# BatteryPowerV2.net
KiCad netlist of a schematic drawn in EAGLE
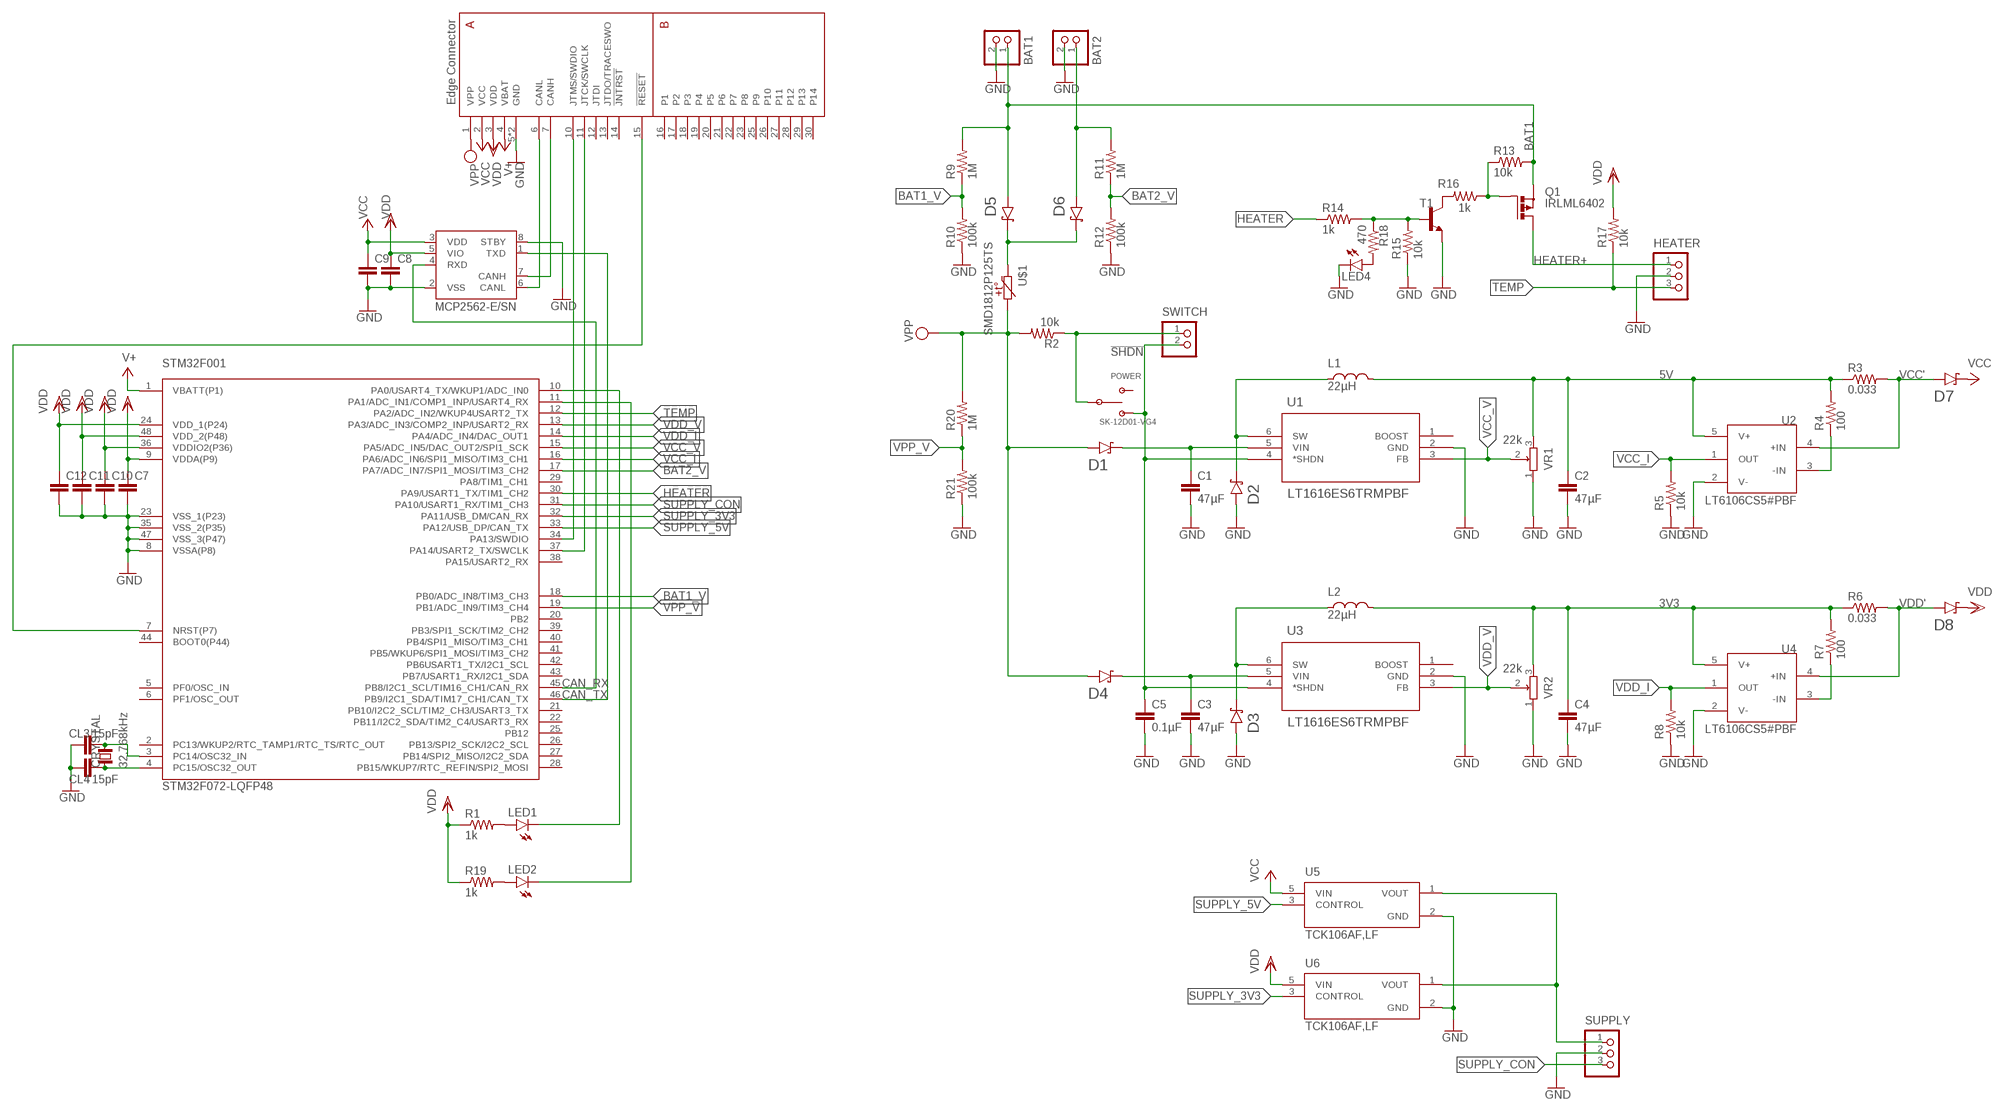
[diagram p0: schematic, sheet 1]

(export (version "E")
  (design (tool "Eeschema 10.0.6"))
  (components
    (comp (ref "BAT1")
      (value "S2B-XH-A")
      (footprint "eagle-import:S2B-XH-A")
      (libsource (lib "eagle-import") (part "S2B-XH-A"))
    )
    (comp (ref "BAT2")
      (value "S2B-XH-A")
      (footprint "eagle-import:S2B-XH-A")
      (libsource (lib "eagle-import") (part "S2B-XH-A"))
    )
    (comp (ref "C1")
      (value "47µF")
      (footprint "eagle-import:C0603")
      (libsource (lib "eagle-import") (part "C-EUC0603"))
    )
    (comp (ref "C2")
      (value "47µF")
      (footprint "eagle-import:C0603")
      (libsource (lib "eagle-import") (part "C-EUC0603"))
    )
    (comp (ref "C3")
      (value "47µF")
      (footprint "eagle-import:C0603")
      (libsource (lib "eagle-import") (part "C-EUC0603"))
    )
    (comp (ref "C4")
      (value "47µF")
      (footprint "eagle-import:C0603")
      (libsource (lib "eagle-import") (part "C-EUC0603"))
    )
    (comp (ref "C5")
      (value "0.1µF")
      (footprint "eagle-import:C0603")
      (libsource (lib "eagle-import") (part "C-EUC0603"))
    )
    (comp (ref "C7")
      (value "C-EUC0603K")
      (footprint "eagle-import:C0603K")
      (libsource (lib "eagle-import") (part "C-EUC0603K"))
    )
    (comp (ref "C8")
      (value "C-EUC0603K")
      (footprint "eagle-import:C0603K")
      (libsource (lib "eagle-import") (part "C-EUC0603K"))
    )
    (comp (ref "C9")
      (value "C-EUC0603K")
      (footprint "eagle-import:C0603K")
      (libsource (lib "eagle-import") (part "C-EUC0603K"))
    )
    (comp (ref "C10")
      (value "C-EUC0603K")
      (footprint "eagle-import:C0603K")
      (libsource (lib "eagle-import") (part "C-EUC0603K"))
    )
    (comp (ref "C11")
      (value "C-EUC0603K")
      (footprint "eagle-import:C0603K")
      (libsource (lib "eagle-import") (part "C-EUC0603K"))
    )
    (comp (ref "C12")
      (value "C-EUC0603K")
      (footprint "eagle-import:C0603K")
      (libsource (lib "eagle-import") (part "C-EUC0603K"))
    )
    (comp (ref "CL3")
      (value "15pF")
      (footprint "eagle-import:C0603K")
      (libsource (lib "eagle-import") (part "C-EUC0603K"))
    )
    (comp (ref "CL4")
      (value "15pF")
      (footprint "eagle-import:C0603K")
      (libsource (lib "eagle-import") (part "C-EUC0603K"))
    )
    (comp (ref "CRYSTAL")
      (value "32.768kHz")
      (footprint "eagle-import:FC-255")
      (libsource (lib "eagle-import") (part "CRYTALFC-255"))
    )
    (comp (ref "D1")
      (value "CUHS20S30")
      (footprint "eagle-import:CUHS20S30")
      (libsource (lib "eagle-import") (part "CUHS20S30"))
    )
    (comp (ref "D2")
      (value "CUHS20S30")
      (footprint "eagle-import:CUHS20S30")
      (libsource (lib "eagle-import") (part "CUHS20S30"))
    )
    (comp (ref "D3")
      (value "CUHS20S30")
      (footprint "eagle-import:CUHS20S30")
      (libsource (lib "eagle-import") (part "CUHS20S30"))
    )
    (comp (ref "D4")
      (value "CUHS20S30")
      (footprint "eagle-import:CUHS20S30")
      (libsource (lib "eagle-import") (part "CUHS20S30"))
    )
    (comp (ref "D5")
      (value "CUHS20S30")
      (footprint "eagle-import:CUHS20S30")
      (libsource (lib "eagle-import") (part "CUHS20S30"))
    )
    (comp (ref "D6")
      (value "CUHS20S30")
      (footprint "eagle-import:CUHS20S30")
      (libsource (lib "eagle-import") (part "CUHS20S30"))
    )
    (comp (ref "D7")
      (value "CUHS20S30")
      (footprint "eagle-import:CUHS20S30")
      (libsource (lib "eagle-import") (part "CUHS20S30"))
    )
    (comp (ref "D8")
      (value "CUHS20S30")
      (footprint "eagle-import:CUHS20S30")
      (libsource (lib "eagle-import") (part "CUHS20S30"))
    )
    (comp (ref "HEATER")
      (value "S3B-PH-K-S")
      (footprint "eagle-import:S3B-PH-K-S")
      (libsource (lib "eagle-import") (part "S3B-PH-K-S"))
    )
    (comp (ref "L1")
      (value "22µH")
      (footprint "eagle-import:NR10050")
      (libsource (lib "eagle-import") (part "NR10050"))
    )
    (comp (ref "L2")
      (value "22µH")
      (footprint "eagle-import:NR10050")
      (libsource (lib "eagle-import") (part "NR10050"))
    )
    (comp (ref "LED1")
      (value "LEDCHIP-LED0603")
      (footprint "eagle-import:CHIP-LED0603")
      (libsource (lib "eagle-import") (part "LEDCHIP-LED0603"))
    )
    (comp (ref "LED2")
      (value "LEDCHIP-LED0603")
      (footprint "eagle-import:CHIP-LED0603")
      (libsource (lib "eagle-import") (part "LEDCHIP-LED0603"))
    )
    (comp (ref "LED4")
      (value "LEDCHIPLED_0603")
      (footprint "eagle-import:CHIPLED_0603")
      (libsource (lib "eagle-import") (part "LEDCHIPLED_0603"))
    )
    (comp (ref "MCP2562")
      (value "MCP2562-E/SN")
      (footprint "eagle-import:SOIC127P600X175-8N")
      (fields (field (name "MF") "Microchip"))
      (libsource (lib "eagle-import") (part "MCP2562-E/SN"))
    )
    (comp (ref "POWER")
      (value "SK-12D01-VG4")
      (footprint "eagle-import:SK-12D01-VG4")
      (libsource (lib "eagle-import") (part "SK-12D01-VG4"))
    )
    (comp (ref "Q1")
      (value "IRLML6402")
      (footprint "eagle-import:SOT-23")
      (libsource (lib "eagle-import") (part "IRLML6402"))
    )
    (comp (ref "R1")
      (value "1k")
      (footprint "eagle-import:R0603")
      (libsource (lib "eagle-import") (part "R-US_R0603"))
    )
    (comp (ref "R2")
      (value "10k")
      (footprint "eagle-import:R0603")
      (libsource (lib "eagle-import") (part "R-US_R0603"))
    )
    (comp (ref "R3")
      (value "0.033")
      (footprint "eagle-import:R0603")
      (libsource (lib "eagle-import") (part "R-US_R0603"))
    )
    (comp (ref "R4")
      (value "100")
      (footprint "eagle-import:R0603")
      (libsource (lib "eagle-import") (part "R-US_R0603"))
    )
    (comp (ref "R5")
      (value "10k")
      (footprint "eagle-import:R0603")
      (libsource (lib "eagle-import") (part "R-US_R0603"))
    )
    (comp (ref "R6")
      (value "0.033")
      (footprint "eagle-import:R0603")
      (libsource (lib "eagle-import") (part "R-US_R0603"))
    )
    (comp (ref "R7")
      (value "100")
      (footprint "eagle-import:R0603")
      (libsource (lib "eagle-import") (part "R-US_R0603"))
    )
    (comp (ref "R8")
      (value "10k")
      (footprint "eagle-import:R0603")
      (libsource (lib "eagle-import") (part "R-US_R0603"))
    )
    (comp (ref "R9")
      (value "1M")
      (footprint "eagle-import:R0603")
      (libsource (lib "eagle-import") (part "R-US_R0603"))
    )
    (comp (ref "R10")
      (value "100k")
      (footprint "eagle-import:R0603")
      (libsource (lib "eagle-import") (part "R-US_R0603"))
    )
    (comp (ref "R11")
      (value "1M")
      (footprint "eagle-import:R0603")
      (libsource (lib "eagle-import") (part "R-US_R0603"))
    )
    (comp (ref "R12")
      (value "100k")
      (footprint "eagle-import:R0603")
      (libsource (lib "eagle-import") (part "R-US_R0603"))
    )
    (comp (ref "R13")
      (value "10k")
      (footprint "eagle-import:R0603")
      (libsource (lib "eagle-import") (part "R-US_R0603"))
    )
    (comp (ref "R14")
      (value "1k")
      (footprint "eagle-import:R0603")
      (libsource (lib "eagle-import") (part "R-US_R0603"))
    )
    (comp (ref "R15")
      (value "10k")
      (footprint "eagle-import:R0603")
      (libsource (lib "eagle-import") (part "R-US_R0603"))
    )
    (comp (ref "R16")
      (value "1k")
      (footprint "eagle-import:R0603")
      (libsource (lib "eagle-import") (part "R-US_R0603"))
    )
    (comp (ref "R17")
      (value "10k")
      (footprint "eagle-import:R0603")
      (libsource (lib "eagle-import") (part "R-US_R0603"))
    )
    (comp (ref "R18")
      (value "470")
      (footprint "eagle-import:R0603")
      (libsource (lib "eagle-import") (part "R-US_R0603"))
    )
    (comp (ref "R19")
      (value "1k")
      (footprint "eagle-import:R0603")
      (libsource (lib "eagle-import") (part "R-US_R0603"))
    )
    (comp (ref "R20")
      (value "1M")
      (footprint "eagle-import:R0603")
      (libsource (lib "eagle-import") (part "R-US_R0603"))
    )
    (comp (ref "R21")
      (value "100k")
      (footprint "eagle-import:R0603")
      (libsource (lib "eagle-import") (part "R-US_R0603"))
    )
    (comp (ref "STM32F001")
      (value "STM32F072-LQFP48")
      (footprint "eagle-import:LQFP48")
      (libsource (lib "eagle-import") (part "STM32F072-LQFP48"))
    )
    (comp (ref "SUPPLY")
      (value "S3B-PH-K-S")
      (footprint "eagle-import:S3B-PH-K-S")
      (libsource (lib "eagle-import") (part "S3B-PH-K-S"))
    )
    (comp (ref "SWITCH")
      (value "S2B-PH-K-S")
      (footprint "eagle-import:S2B-PH-K-S")
      (libsource (lib "eagle-import") (part "S2B-PH-K-S"))
    )
    (comp (ref "T1")
      (value "-NPN-SOT23-EBC")
      (footprint "eagle-import:SOT23-EBC")
      (libsource (lib "eagle-import") (part "-NPN-SOT23-EBC"))
    )
    (comp (ref "U$1")
      (value "SMD1812P125TS")
      (footprint "eagle-import:SMD1812P")
      (libsource (lib "eagle-import") (part "SMD1812P125TS"))
    )
    (comp (ref "U$2")
      (value "EDGE30")
      (footprint "eagle-import:EDGE30")
      (libsource (lib "eagle-import") (part "EDGE30"))
    )
    (comp (ref "U1")
      (value "LT1616ES6TRMPBF")
      (footprint "eagle-import:SOT-6_S")
      (fields (field (name "MF") "Analog Devices") (field (name "MP") "LT1616ES6#TRMPBF"))
      (libsource (lib "eagle-import") (part "LT1616ES6TRMPBF"))
    )
    (comp (ref "U2")
      (value "LT6106CS5#PBF")
      (footprint "eagle-import:SOT95P280X100-5N_LT6106CS5#PBF")
      (fields (field (name "MF") "Linear Technology"))
      (libsource (lib "eagle-import") (part "LT6106CS5#PBF"))
    )
    (comp (ref "U3")
      (value "LT1616ES6TRMPBF")
      (footprint "eagle-import:SOT-6_S")
      (fields (field (name "MF") "Analog Devices") (field (name "MP") "LT1616ES6#TRMPBF"))
      (libsource (lib "eagle-import") (part "LT1616ES6TRMPBF"))
    )
    (comp (ref "U4")
      (value "LT6106CS5#PBF")
      (footprint "eagle-import:SOT95P280X100-5N_LT6106CS5#PBF")
      (fields (field (name "MF") "Linear Technology"))
      (libsource (lib "eagle-import") (part "LT6106CS5#PBF"))
    )
    (comp (ref "U5")
      (value "TCK106AF,LF")
      (footprint "eagle-import:IC_TCK106AF,LF")
      (fields (field (name "MF") "Toshiba Semiconductor"))
      (libsource (lib "eagle-import") (part "TCK106AF,LF"))
    )
    (comp (ref "U6")
      (value "TCK106AF,LF")
      (footprint "eagle-import:IC_TCK106AF,LF")
      (fields (field (name "MF") "Toshiba Semiconductor"))
      (libsource (lib "eagle-import") (part "TCK106AF,LF"))
    )
    (comp (ref "VR1")
      (value "22k")
      (footprint "eagle-import:PVZ3A")
      (libsource (lib "eagle-import") (part "PVZ3A"))
    )
    (comp (ref "VR2")
      (value "22k")
      (footprint "eagle-import:PVZ3A")
      (libsource (lib "eagle-import") (part "PVZ3A"))
    )
  )
  (nets
    (net (code "1") (name "/3V3") (class "Default")
      (node (ref "C4") (pin "1") (pinfunction "1_1") (pintype "passive"))
      (node (ref "L2") (pin "2") (pinfunction "2_2") (pintype "bidirectional"))
      (node (ref "R6") (pin "1") (pinfunction "1_1") (pintype "passive"))
      (node (ref "R7") (pin "2") (pinfunction "2_2") (pintype "passive"))
      (node (ref "U4") (pin "5") (pinfunction "V+_5") (pintype "power_in"))
      (node (ref "VR2") (pin "3") (pinfunction "3_3") (pintype "bidirectional"))
    )
    (net (code "2") (name "/5V") (class "Default")
      (node (ref "C2") (pin "1") (pinfunction "1_1") (pintype "passive"))
      (node (ref "L1") (pin "2") (pinfunction "2_2") (pintype "bidirectional"))
      (node (ref "R3") (pin "1") (pinfunction "1_1") (pintype "passive"))
      (node (ref "R4") (pin "2") (pinfunction "2_2") (pintype "passive"))
      (node (ref "U2") (pin "5") (pinfunction "V+_5") (pintype "power_in"))
      (node (ref "VR1") (pin "3") (pinfunction "3_3") (pintype "bidirectional"))
    )
    (net (code "3") (name "/BAT1") (class "Default")
      (node (ref "BAT1") (pin "1") (pinfunction "1_1") (pintype "passive"))
      (node (ref "D5") (pin "A") (pinfunction "A_A") (pintype "bidirectional"))
      (node (ref "Q1") (pin "P2") (pinfunction "S_P2") (pintype "passive"))
      (node (ref "R13") (pin "2") (pinfunction "2_2") (pintype "passive"))
      (node (ref "R9") (pin "2") (pinfunction "2_2") (pintype "passive"))
    )
    (net (code "4") (name "/CAN_RX") (class "Default")
      (node (ref "MCP2562") (pin "4") (pinfunction "RXD_4") (pintype "output"))
      (node (ref "STM32F001") (pin "45") (pinfunction "PB8/I2C1_SCL/TIM16_CH1/CAN_RX_45") (pintype "bidirectional"))
    )
    (net (code "5") (name "/CAN_TX") (class "Default")
      (node (ref "MCP2562") (pin "1") (pinfunction "TXD_1") (pintype "input"))
      (node (ref "STM32F001") (pin "46") (pinfunction "PB9/I2C1_SDA/TIM17_CH1/CAN_TX_46") (pintype "bidirectional"))
    )
    (net (code "6") (name "/HEATER+") (class "Default")
      (node (ref "HEATER") (pin "1") (pinfunction "1_1") (pintype "passive"))
      (node (ref "Q1") (pin "P3") (pinfunction "D_P3") (pintype "passive"))
    )
    (net (code "7") (name "/VCC'") (class "Default")
      (node (ref "D7") (pin "A") (pinfunction "A_A") (pintype "bidirectional"))
      (node (ref "R3") (pin "2") (pinfunction "2_2") (pintype "passive"))
      (node (ref "U2") (pin "4") (pinfunction "+IN_4") (pintype "input"))
    )
    (net (code "8") (name "/VDD'") (class "Default")
      (node (ref "D8") (pin "A") (pinfunction "A_A") (pintype "bidirectional"))
      (node (ref "R6") (pin "2") (pinfunction "2_2") (pintype "passive"))
      (node (ref "U4") (pin "4") (pinfunction "+IN_4") (pintype "input"))
    )
    (net (code "9") (name "/~{SHDN}") (class "Default")
      (node (ref "C5") (pin "1") (pinfunction "1_1") (pintype "passive"))
      (node (ref "POWER") (pin "B") (pinfunction "B_B") (pintype "bidirectional"))
      (node (ref "SWITCH") (pin "2") (pinfunction "2_2") (pintype "passive"))
      (node (ref "U1") (pin "4") (pinfunction "*SHDN_4") (pintype "input"))
      (node (ref "U3") (pin "4") (pinfunction "*SHDN_4") (pintype "input"))
    )
    (net (code "10") (name "BAT1_V") (class "Default")
      (node (ref "R10") (pin "2") (pinfunction "2_2") (pintype "passive"))
      (node (ref "R9") (pin "1") (pinfunction "1_1") (pintype "passive"))
      (node (ref "STM32F001") (pin "18") (pinfunction "PB0/ADC_IN8/TIM3_CH3_18") (pintype "bidirectional"))
    )
    (net (code "11") (name "BAT2_V") (class "Default")
      (node (ref "R11") (pin "1") (pinfunction "1_1") (pintype "passive"))
      (node (ref "R12") (pin "2") (pinfunction "2_2") (pintype "passive"))
      (node (ref "STM32F001") (pin "17") (pinfunction "PA7/ADC_IN7/SPI1_MOSI/TIM3_CH2_17") (pintype "bidirectional"))
    )
    (net (code "12") (name "GND") (class "Default")
      (node (ref "BAT1") (pin "2") (pinfunction "2_2") (pintype "passive"))
      (node (ref "BAT2") (pin "2") (pinfunction "2_2") (pintype "passive"))
      (node (ref "C1") (pin "2") (pinfunction "2_2") (pintype "passive"))
      (node (ref "C10") (pin "2") (pinfunction "2_2") (pintype "passive"))
      (node (ref "C11") (pin "2") (pinfunction "2_2") (pintype "passive"))
      (node (ref "C12") (pin "2") (pinfunction "2_2") (pintype "passive"))
      (node (ref "C2") (pin "2") (pinfunction "2_2") (pintype "passive"))
      (node (ref "C3") (pin "2") (pinfunction "2_2") (pintype "passive"))
      (node (ref "C4") (pin "2") (pinfunction "2_2") (pintype "passive"))
      (node (ref "C5") (pin "2") (pinfunction "2_2") (pintype "passive"))
      (node (ref "C7") (pin "2") (pinfunction "2_2") (pintype "passive"))
      (node (ref "C8") (pin "2") (pinfunction "2_2") (pintype "passive"))
      (node (ref "C9") (pin "2") (pinfunction "2_2") (pintype "passive"))
      (node (ref "CL3") (pin "1") (pinfunction "1_1") (pintype "passive"))
      (node (ref "CL4") (pin "1") (pinfunction "1_1") (pintype "passive"))
      (node (ref "D2") (pin "A") (pinfunction "A_A") (pintype "bidirectional"))
      (node (ref "D3") (pin "A") (pinfunction "A_A") (pintype "bidirectional"))
      (node (ref "HEATER") (pin "2") (pinfunction "2_2") (pintype "passive"))
      (node (ref "LED4") (pin "C") (pinfunction "C_C") (pintype "passive"))
      (node (ref "MCP2562") (pin "2") (pinfunction "VSS_2") (pintype "power_in"))
      (node (ref "MCP2562") (pin "8") (pinfunction "STBY_8") (pintype "input"))
      (node (ref "R10") (pin "1") (pinfunction "1_1") (pintype "passive"))
      (node (ref "R12") (pin "1") (pinfunction "1_1") (pintype "passive"))
      (node (ref "R15") (pin "1") (pinfunction "1_1") (pintype "passive"))
      (node (ref "R21") (pin "1") (pinfunction "1_1") (pintype "passive"))
      (node (ref "R5") (pin "1") (pinfunction "1_1") (pintype "passive"))
      (node (ref "R8") (pin "1") (pinfunction "1_1") (pintype "passive"))
      (node (ref "STM32F001") (pin "23") (pinfunction "VSS_1(P23)_23") (pintype "bidirectional"))
      (node (ref "STM32F001") (pin "35") (pinfunction "VSS_2(P35)_35") (pintype "bidirectional"))
      (node (ref "STM32F001") (pin "47") (pinfunction "VSS_3(P47)_47") (pintype "bidirectional"))
      (node (ref "STM32F001") (pin "8") (pinfunction "VSSA(P8)_8") (pintype "bidirectional"))
      (node (ref "SUPPLY") (pin "2") (pinfunction "2_2") (pintype "passive"))
      (node (ref "T1") (pin "E") (pinfunction "E_E") (pintype "passive"))
      (node (ref "U$2") (pin "5") (pinfunction "GND_5") (pintype "power_in"))
      (node (ref "U$2") (pin "8") (pinfunction "GND_8") (pintype "power_in"))
      (node (ref "U1") (pin "2") (pinfunction "GND_2") (pintype "power_in"))
      (node (ref "U2") (pin "2") (pinfunction "V-_2") (pintype "power_in"))
      (node (ref "U3") (pin "2") (pinfunction "GND_2") (pintype "power_in"))
      (node (ref "U4") (pin "2") (pinfunction "V-_2") (pintype "power_in"))
      (node (ref "U5") (pin "2") (pinfunction "GND_2") (pintype "power_in"))
      (node (ref "U6") (pin "2") (pinfunction "GND_2") (pintype "power_in"))
      (node (ref "VR1") (pin "1") (pinfunction "1_1") (pintype "bidirectional"))
      (node (ref "VR2") (pin "1") (pinfunction "1_1") (pintype "bidirectional"))
    )
    (net (code "13") (name "HEATER") (class "Default")
      (node (ref "R14") (pin "1") (pinfunction "1_1") (pintype "passive"))
      (node (ref "STM32F001") (pin "30") (pinfunction "PA9/USART1_TX/TIM1_CH2_30") (pintype "bidirectional"))
    )
    (net (code "14") (name "Net-(BAT2-Pad1)") (class "Default")
      (node (ref "BAT2") (pin "1") (pinfunction "1_1") (pintype "passive"))
      (node (ref "D6") (pin "A") (pinfunction "A_A") (pintype "bidirectional"))
      (node (ref "R11") (pin "2") (pinfunction "2_2") (pintype "passive"))
    )
    (net (code "15") (name "Net-(LED1-PadA)") (class "Default")
      (node (ref "LED1") (pin "A") (pinfunction "A_A") (pintype "passive"))
      (node (ref "R1") (pin "2") (pinfunction "2_2") (pintype "passive"))
    )
    (net (code "16") (name "Net-(LED2-PadA)") (class "Default")
      (node (ref "LED2") (pin "A") (pinfunction "A_A") (pintype "passive"))
      (node (ref "R19") (pin "2") (pinfunction "2_2") (pintype "passive"))
    )
    (net (code "17") (name "Net-(LED4-PadA)") (class "Default")
      (node (ref "LED4") (pin "A") (pinfunction "A_A") (pintype "passive"))
      (node (ref "R18") (pin "2") (pinfunction "2_2") (pintype "passive"))
    )
    (net (code "18") (name "Net-(MCP2562-CANH)") (class "Default")
      (node (ref "MCP2562") (pin "7") (pinfunction "CANH_7") (pintype "input"))
      (node (ref "U$2") (pin "7") (pinfunction "CANH_7") (pintype "bidirectional"))
    )
    (net (code "19") (name "Net-(MCP2562-CANL)") (class "Default")
      (node (ref "MCP2562") (pin "6") (pinfunction "CANL_6") (pintype "input"))
      (node (ref "U$2") (pin "6") (pinfunction "CANL_6") (pintype "bidirectional"))
    )
    (net (code "20") (name "Net-(POWER-PadC)") (class "Default")
      (node (ref "POWER") (pin "C") (pinfunction "C_C") (pintype "bidirectional"))
      (node (ref "R2") (pin "1") (pinfunction "1_1") (pintype "passive"))
      (node (ref "SWITCH") (pin "1") (pinfunction "1_1") (pintype "passive"))
    )
    (net (code "21") (name "Net-(Q1-G)") (class "Default")
      (node (ref "Q1") (pin "P1") (pinfunction "G_P1") (pintype "passive"))
      (node (ref "R13") (pin "1") (pinfunction "1_1") (pintype "passive"))
      (node (ref "R16") (pin "1") (pinfunction "1_1") (pintype "passive"))
    )
    (net (code "22") (name "Net-(R14-Pad2)") (class "Default")
      (node (ref "R14") (pin "2") (pinfunction "2_2") (pintype "passive"))
      (node (ref "R15") (pin "2") (pinfunction "2_2") (pintype "passive"))
      (node (ref "R18") (pin "1") (pinfunction "1_1") (pintype "passive"))
      (node (ref "T1") (pin "B") (pinfunction "B_B") (pintype "passive"))
    )
    (net (code "23") (name "Net-(R16-Pad2)") (class "Default")
      (node (ref "R16") (pin "2") (pinfunction "2_2") (pintype "passive"))
      (node (ref "T1") (pin "C") (pinfunction "C_C") (pintype "passive"))
    )
    (net (code "24") (name "Net-(STM32F001-NRST(P7))") (class "Default")
      (node (ref "STM32F001") (pin "7") (pinfunction "NRST(P7)_7") (pintype "bidirectional"))
      (node (ref "U$2") (pin "15") (pinfunction "~{RESET}_15") (pintype "bidirectional"))
    )
    (net (code "25") (name "Net-(STM32F001-PA0{slash}USART4_TX{slash}WKUP1{slash}ADC_IN0)") (class "Default")
      (node (ref "LED1") (pin "C") (pinfunction "C_C") (pintype "passive"))
      (node (ref "STM32F001") (pin "10") (pinfunction "PA0/USART4_TX/WKUP1/ADC_IN0_10") (pintype "bidirectional"))
    )
    (net (code "26") (name "Net-(STM32F001-PA1{slash}ADC_IN1{slash}COMP1_INP{slash}USART4_RX)") (class "Default")
      (node (ref "LED2") (pin "C") (pinfunction "C_C") (pintype "passive"))
      (node (ref "STM32F001") (pin "11") (pinfunction "PA1/ADC_IN1/COMP1_INP/USART4_RX_11") (pintype "bidirectional"))
    )
    (net (code "27") (name "Net-(STM32F001-PA13{slash}SWDIO)") (class "Default")
      (node (ref "STM32F001") (pin "34") (pinfunction "PA13/SWDIO_34") (pintype "bidirectional"))
      (node (ref "U$2") (pin "10") (pinfunction "JTMS/SWDIO_10") (pintype "bidirectional"))
    )
    (net (code "28") (name "Net-(STM32F001-PA14{slash}USART2_TX{slash}SWCLK)") (class "Default")
      (node (ref "STM32F001") (pin "37") (pinfunction "PA14/USART2_TX/SWCLK_37") (pintype "bidirectional"))
      (node (ref "U$2") (pin "11") (pinfunction "JTCK/SWCLK_11") (pintype "bidirectional"))
    )
    (net (code "29") (name "Net-(STM32F001-PC14{slash}OSC32_IN)") (class "Default")
      (node (ref "CL3") (pin "2") (pinfunction "2_2") (pintype "passive"))
      (node (ref "CRYSTAL") (pin "2") (pinfunction "2_2") (pintype "passive"))
      (node (ref "STM32F001") (pin "3") (pinfunction "PC14/OSC32_IN_3") (pintype "bidirectional"))
    )
    (net (code "30") (name "Net-(STM32F001-PC15{slash}OSC32_OUT)") (class "Default")
      (node (ref "CL4") (pin "2") (pinfunction "2_2") (pintype "passive"))
      (node (ref "CRYSTAL") (pin "1") (pinfunction "1_1") (pintype "passive"))
      (node (ref "STM32F001") (pin "4") (pinfunction "PC15/OSC32_OUT_4") (pintype "bidirectional"))
    )
    (net (code "31") (name "Net-(U$1-P1)") (class "Default")
      (node (ref "D5") (pin "C") (pinfunction "C_C") (pintype "bidirectional"))
      (node (ref "D6") (pin "C") (pinfunction "C_C") (pintype "bidirectional"))
      (node (ref "U$1") (pin "1") (pinfunction "P1_1") (pintype "bidirectional"))
    )
    (net (code "32") (name "Net-(U1-SW)") (class "Default")
      (node (ref "D2") (pin "C") (pinfunction "C_C") (pintype "bidirectional"))
      (node (ref "L1") (pin "1") (pinfunction "1_1") (pintype "bidirectional"))
      (node (ref "U1") (pin "6") (pinfunction "SW_6") (pintype "output"))
    )
    (net (code "33") (name "Net-(U1-VIN)") (class "Default")
      (node (ref "C1") (pin "1") (pinfunction "1_1") (pintype "passive"))
      (node (ref "D1") (pin "C") (pinfunction "C_C") (pintype "bidirectional"))
      (node (ref "U1") (pin "5") (pinfunction "VIN_5") (pintype "power_in"))
    )
    (net (code "34") (name "Net-(U2--IN)") (class "Default")
      (node (ref "R4") (pin "1") (pinfunction "1_1") (pintype "passive"))
      (node (ref "U2") (pin "3") (pinfunction "-IN_3") (pintype "input"))
    )
    (net (code "35") (name "Net-(U3-SW)") (class "Default")
      (node (ref "D3") (pin "C") (pinfunction "C_C") (pintype "bidirectional"))
      (node (ref "L2") (pin "1") (pinfunction "1_1") (pintype "bidirectional"))
      (node (ref "U3") (pin "6") (pinfunction "SW_6") (pintype "output"))
    )
    (net (code "36") (name "Net-(U3-VIN)") (class "Default")
      (node (ref "C3") (pin "1") (pinfunction "1_1") (pintype "passive"))
      (node (ref "D4") (pin "C") (pinfunction "C_C") (pintype "bidirectional"))
      (node (ref "U3") (pin "5") (pinfunction "VIN_5") (pintype "power_in"))
    )
    (net (code "37") (name "Net-(U4--IN)") (class "Default")
      (node (ref "R7") (pin "1") (pinfunction "1_1") (pintype "passive"))
      (node (ref "U4") (pin "3") (pinfunction "-IN_3") (pintype "input"))
    )
    (net (code "38") (name "Net-(U5-VOUT)") (class "Default")
      (node (ref "SUPPLY") (pin "1") (pinfunction "1_1") (pintype "passive"))
      (node (ref "U5") (pin "1") (pinfunction "VOUT_1") (pintype "output"))
      (node (ref "U6") (pin "1") (pinfunction "VOUT_1") (pintype "output"))
    )
    (net (code "39") (name "SUPPLY_3V3") (class "Default")
      (node (ref "STM32F001") (pin "32") (pinfunction "PA11/USB_DM/CAN_RX_32") (pintype "bidirectional"))
      (node (ref "U6") (pin "3") (pinfunction "CONTROL_3") (pintype "input"))
    )
    (net (code "40") (name "SUPPLY_5V") (class "Default")
      (node (ref "STM32F001") (pin "33") (pinfunction "PA12/USB_DP/CAN_TX_33") (pintype "bidirectional"))
      (node (ref "U5") (pin "3") (pinfunction "CONTROL_3") (pintype "input"))
    )
    (net (code "41") (name "SUPPLY_CON") (class "Default")
      (node (ref "STM32F001") (pin "31") (pinfunction "PA10/USART1_RX/TIM1_CH3_31") (pintype "bidirectional"))
      (node (ref "SUPPLY") (pin "3") (pinfunction "3_3") (pintype "passive"))
    )
    (net (code "42") (name "TEMP") (class "Default")
      (node (ref "HEATER") (pin "3") (pinfunction "3_3") (pintype "passive"))
      (node (ref "R17") (pin "1") (pinfunction "1_1") (pintype "passive"))
      (node (ref "STM32F001") (pin "12") (pinfunction "PA2/ADC_IN2/WKUP4USART2_TX_12") (pintype "bidirectional"))
    )
    (net (code "43") (name "V+") (class "Default")
      (node (ref "STM32F001") (pin "1") (pinfunction "VBATT(P1)_1") (pintype "bidirectional"))
      (node (ref "U$2") (pin "4") (pinfunction "VBAT_4") (pintype "power_in"))
    )
    (net (code "44") (name "VCC") (class "Default")
      (node (ref "C9") (pin "1") (pinfunction "1_1") (pintype "passive"))
      (node (ref "D7") (pin "C") (pinfunction "C_C") (pintype "bidirectional"))
      (node (ref "MCP2562") (pin "3") (pinfunction "VDD_3") (pintype "power_in"))
      (node (ref "U$2") (pin "2") (pinfunction "VCC_2") (pintype "power_in"))
      (node (ref "U5") (pin "5") (pinfunction "VIN_5") (pintype "input"))
    )
    (net (code "45") (name "VCC_I") (class "Default")
      (node (ref "R5") (pin "2") (pinfunction "2_2") (pintype "passive"))
      (node (ref "STM32F001") (pin "16") (pinfunction "PA6/ADC_IN6/SPI1_MISO/TIM3_CH1_16") (pintype "bidirectional"))
      (node (ref "U2") (pin "1") (pinfunction "OUT_1") (pintype "output"))
    )
    (net (code "46") (name "VCC_V") (class "Default")
      (node (ref "STM32F001") (pin "15") (pinfunction "PA5/ADC_IN5/DAC_OUT2/SPI1_SCK_15") (pintype "bidirectional"))
      (node (ref "U1") (pin "3") (pinfunction "FB_3") (pintype "input"))
      (node (ref "VR1") (pin "2") (pinfunction "2_2") (pintype "bidirectional"))
    )
    (net (code "47") (name "VDD") (class "Default")
      (node (ref "C10") (pin "1") (pinfunction "1_1") (pintype "passive"))
      (node (ref "C11") (pin "1") (pinfunction "1_1") (pintype "passive"))
      (node (ref "C12") (pin "1") (pinfunction "1_1") (pintype "passive"))
      (node (ref "C7") (pin "1") (pinfunction "1_1") (pintype "passive"))
      (node (ref "C8") (pin "1") (pinfunction "1_1") (pintype "passive"))
      (node (ref "D8") (pin "C") (pinfunction "C_C") (pintype "bidirectional"))
      (node (ref "MCP2562") (pin "5") (pinfunction "VIO_5") (pintype "power_in"))
      (node (ref "R1") (pin "1") (pinfunction "1_1") (pintype "passive"))
      (node (ref "R17") (pin "2") (pinfunction "2_2") (pintype "passive"))
      (node (ref "R19") (pin "1") (pinfunction "1_1") (pintype "passive"))
      (node (ref "STM32F001") (pin "24") (pinfunction "VDD_1(P24)_24") (pintype "bidirectional"))
      (node (ref "STM32F001") (pin "36") (pinfunction "VDDIO2(P36)_36") (pintype "bidirectional"))
      (node (ref "STM32F001") (pin "48") (pinfunction "VDD_2(P48)_48") (pintype "bidirectional"))
      (node (ref "STM32F001") (pin "9") (pinfunction "VDDA(P9)_9") (pintype "bidirectional"))
      (node (ref "U$2") (pin "3") (pinfunction "VDD_3") (pintype "power_in"))
      (node (ref "U6") (pin "5") (pinfunction "VIN_5") (pintype "input"))
    )
    (net (code "48") (name "VDD_I") (class "Default")
      (node (ref "R8") (pin "2") (pinfunction "2_2") (pintype "passive"))
      (node (ref "STM32F001") (pin "14") (pinfunction "PA4/ADC_IN4/DAC_OUT1_14") (pintype "bidirectional"))
      (node (ref "U4") (pin "1") (pinfunction "OUT_1") (pintype "output"))
    )
    (net (code "49") (name "VDD_V") (class "Default")
      (node (ref "STM32F001") (pin "13") (pinfunction "PA3/ADC_IN3/COMP2_INP/USART2_RX_13") (pintype "bidirectional"))
      (node (ref "U3") (pin "3") (pinfunction "FB_3") (pintype "input"))
      (node (ref "VR2") (pin "2") (pinfunction "2_2") (pintype "bidirectional"))
    )
    (net (code "50") (name "VPP") (class "Default")
      (node (ref "D1") (pin "A") (pinfunction "A_A") (pintype "bidirectional"))
      (node (ref "D4") (pin "A") (pinfunction "A_A") (pintype "bidirectional"))
      (node (ref "R2") (pin "2") (pinfunction "2_2") (pintype "passive"))
      (node (ref "R20") (pin "2") (pinfunction "2_2") (pintype "passive"))
      (node (ref "U$1") (pin "2") (pinfunction "P2_2") (pintype "bidirectional"))
      (node (ref "U$2") (pin "1") (pinfunction "VPP_1") (pintype "power_in"))
    )
    (net (code "51") (name "VPP_V") (class "Default")
      (node (ref "R20") (pin "1") (pinfunction "1_1") (pintype "passive"))
      (node (ref "R21") (pin "2") (pinfunction "2_2") (pintype "passive"))
      (node (ref "STM32F001") (pin "19") (pinfunction "PB1/ADC_IN9/TIM3_CH4_19") (pintype "bidirectional"))
    )
    (net (code "52") (name "unconnected-(POWER-PadA)") (class "Default")
      (node (ref "POWER") (pin "A") (pinfunction "A_A") (pintype "bidirectional"))
    )
    (net (code "53") (name "unconnected-(STM32F001-BOOT0(P44)-Pad44)") (class "Default")
      (node (ref "STM32F001") (pin "44") (pinfunction "BOOT0(P44)_44") (pintype "bidirectional"))
    )
    (net (code "54") (name "unconnected-(STM32F001-PA8{slash}TIM1_CH1-Pad29)") (class "Default")
      (node (ref "STM32F001") (pin "29") (pinfunction "PA8/TIM1_CH1_29") (pintype "bidirectional"))
    )
    (net (code "55") (name "unconnected-(STM32F001-PA15{slash}USART2_RX-Pad38)") (class "Default")
      (node (ref "STM32F001") (pin "38") (pinfunction "PA15/USART2_RX_38") (pintype "bidirectional"))
    )
    (net (code "56") (name "unconnected-(STM32F001-PB2-Pad20)") (class "Default")
      (node (ref "STM32F001") (pin "20") (pinfunction "PB2_20") (pintype "bidirectional"))
    )
    (net (code "57") (name "unconnected-(STM32F001-PB3{slash}SPI1_SCK{slash}TIM2_CH2-Pad39)") (class "Default")
      (node (ref "STM32F001") (pin "39") (pinfunction "PB3/SPI1_SCK/TIM2_CH2_39") (pintype "bidirectional"))
    )
    (net (code "58") (name "unconnected-(STM32F001-PB4{slash}SPI1_MISO{slash}TIM3_CH1-Pad40)") (class "Default")
      (node (ref "STM32F001") (pin "40") (pinfunction "PB4/SPI1_MISO/TIM3_CH1_40") (pintype "bidirectional"))
    )
    (net (code "59") (name "unconnected-(STM32F001-PB5{slash}WKUP6{slash}SPI1_MOSI{slash}TIM3_CH2-Pad41)") (class "Default")
      (node (ref "STM32F001") (pin "41") (pinfunction "PB5/WKUP6/SPI1_MOSI/TIM3_CH2_41") (pintype "bidirectional"))
    )
    (net (code "60") (name "unconnected-(STM32F001-PB6USART1_TX{slash}I2C1_SCL-Pad42)") (class "Default")
      (node (ref "STM32F001") (pin "42") (pinfunction "PB6USART1_TX/I2C1_SCL_42") (pintype "bidirectional"))
    )
    (net (code "61") (name "unconnected-(STM32F001-PB7{slash}USART1_RX{slash}I2C1_SDA-Pad43)") (class "Default")
      (node (ref "STM32F001") (pin "43") (pinfunction "PB7/USART1_RX/I2C1_SDA_43") (pintype "bidirectional"))
    )
    (net (code "62") (name "unconnected-(STM32F001-PB10{slash}I2C2_SCL{slash}TIM2_CH3{slash}USART3_TX-Pad21)") (class "Default")
      (node (ref "STM32F001") (pin "21") (pinfunction "PB10/I2C2_SCL/TIM2_CH3/USART3_TX_21") (pintype "bidirectional"))
    )
    (net (code "63") (name "unconnected-(STM32F001-PB11{slash}I2C2_SDA{slash}TIM2_C4{slash}USART3_RX-Pad22)") (class "Default")
      (node (ref "STM32F001") (pin "22") (pinfunction "PB11/I2C2_SDA/TIM2_C4/USART3_RX_22") (pintype "bidirectional"))
    )
    (net (code "64") (name "unconnected-(STM32F001-PB12-Pad25)") (class "Default")
      (node (ref "STM32F001") (pin "25") (pinfunction "PB12_25") (pintype "bidirectional"))
    )
    (net (code "65") (name "unconnected-(STM32F001-PB13{slash}SPI2_SCK{slash}I2C2_SCL-Pad26)") (class "Default")
      (node (ref "STM32F001") (pin "26") (pinfunction "PB13/SPI2_SCK/I2C2_SCL_26") (pintype "bidirectional"))
    )
    (net (code "66") (name "unconnected-(STM32F001-PB14{slash}SPI2_MISO{slash}I2C2_SDA-Pad27)") (class "Default")
      (node (ref "STM32F001") (pin "27") (pinfunction "PB14/SPI2_MISO/I2C2_SDA_27") (pintype "bidirectional"))
    )
    (net (code "67") (name "unconnected-(STM32F001-PB15{slash}WKUP7{slash}RTC_REFIN{slash}SPI2_MOSI-Pad28)") (class "Default")
      (node (ref "STM32F001") (pin "28") (pinfunction "PB15/WKUP7/RTC_REFIN/SPI2_MOSI_28") (pintype "bidirectional"))
    )
    (net (code "68") (name "unconnected-(STM32F001-PC13{slash}WKUP2{slash}RTC_TAMP1{slash}RTC_TS{slash}RTC_OUT-Pad2)") (class "Default")
      (node (ref "STM32F001") (pin "2") (pinfunction "PC13/WKUP2/RTC_TAMP1/RTC_TS/RTC_OUT_2") (pintype "bidirectional"))
    )
    (net (code "69") (name "unconnected-(STM32F001-PF0{slash}OSC_IN-Pad5)") (class "Default")
      (node (ref "STM32F001") (pin "5") (pinfunction "PF0/OSC_IN_5") (pintype "bidirectional"))
    )
    (net (code "70") (name "unconnected-(STM32F001-PF1{slash}OSC_OUT-Pad6)") (class "Default")
      (node (ref "STM32F001") (pin "6") (pinfunction "PF1/OSC_OUT_6") (pintype "bidirectional"))
    )
    (net (code "71") (name "unconnected-(U$2-JTDI-Pad12)") (class "Default")
      (node (ref "U$2") (pin "12") (pinfunction "JTDI_12") (pintype "bidirectional"))
    )
    (net (code "72") (name "unconnected-(U$2-JTDO{slash}TRACESWO-Pad13)") (class "Default")
      (node (ref "U$2") (pin "13") (pinfunction "JTDO/TRACESWO_13") (pintype "bidirectional"))
    )
    (net (code "73") (name "unconnected-(U$2-P1-Pad16)") (class "Default")
      (node (ref "U$2") (pin "16") (pinfunction "P1_16") (pintype "bidirectional"))
    )
    (net (code "74") (name "unconnected-(U$2-P2-Pad17)") (class "Default")
      (node (ref "U$2") (pin "17") (pinfunction "P2_17") (pintype "bidirectional"))
    )
    (net (code "75") (name "unconnected-(U$2-P3-Pad18)") (class "Default")
      (node (ref "U$2") (pin "18") (pinfunction "P3_18") (pintype "bidirectional"))
    )
    (net (code "76") (name "unconnected-(U$2-P4-Pad19)") (class "Default")
      (node (ref "U$2") (pin "19") (pinfunction "P4_19") (pintype "bidirectional"))
    )
    (net (code "77") (name "unconnected-(U$2-P5-Pad20)") (class "Default")
      (node (ref "U$2") (pin "20") (pinfunction "P5_20") (pintype "bidirectional"))
    )
    (net (code "78") (name "unconnected-(U$2-P6-Pad21)") (class "Default")
      (node (ref "U$2") (pin "21") (pinfunction "P6_21") (pintype "bidirectional"))
    )
    (net (code "79") (name "unconnected-(U$2-P7-Pad22)") (class "Default")
      (node (ref "U$2") (pin "22") (pinfunction "P7_22") (pintype "bidirectional"))
    )
    (net (code "80") (name "unconnected-(U$2-P8-Pad23)") (class "Default")
      (node (ref "U$2") (pin "23") (pinfunction "P8_23") (pintype "bidirectional"))
    )
    (net (code "81") (name "unconnected-(U$2-P9-Pad25)") (class "Default")
      (node (ref "U$2") (pin "25") (pinfunction "P9_25") (pintype "bidirectional"))
    )
    (net (code "82") (name "unconnected-(U$2-P10-Pad26)") (class "Default")
      (node (ref "U$2") (pin "26") (pinfunction "P10_26") (pintype "bidirectional"))
    )
    (net (code "83") (name "unconnected-(U$2-P11-Pad27)") (class "Default")
      (node (ref "U$2") (pin "27") (pinfunction "P11_27") (pintype "bidirectional"))
    )
    (net (code "84") (name "unconnected-(U$2-P12-Pad28)") (class "Default")
      (node (ref "U$2") (pin "28") (pinfunction "P12_28") (pintype "bidirectional"))
    )
    (net (code "85") (name "unconnected-(U$2-P13-Pad29)") (class "Default")
      (node (ref "U$2") (pin "29") (pinfunction "P13_29") (pintype "bidirectional"))
    )
    (net (code "86") (name "unconnected-(U$2-P14-Pad30)") (class "Default")
      (node (ref "U$2") (pin "30") (pinfunction "P14_30") (pintype "bidirectional"))
    )
    (net (code "87") (name "unconnected-(U$2-~{JNTRST}-Pad14)") (class "Default")
      (node (ref "U$2") (pin "14") (pinfunction "~{JNTRST}_14") (pintype "bidirectional"))
    )
    (net (code "88") (name "unconnected-(U1-BOOST-Pad1)") (class "Default")
      (node (ref "U1") (pin "1") (pinfunction "BOOST_1") (pintype "input"))
    )
    (net (code "89") (name "unconnected-(U3-BOOST-Pad1)") (class "Default")
      (node (ref "U3") (pin "1") (pinfunction "BOOST_1") (pintype "input"))
    )
  )
)
